# wordle_display.net
KiCad netlist of a schematic drawn in EAGLE
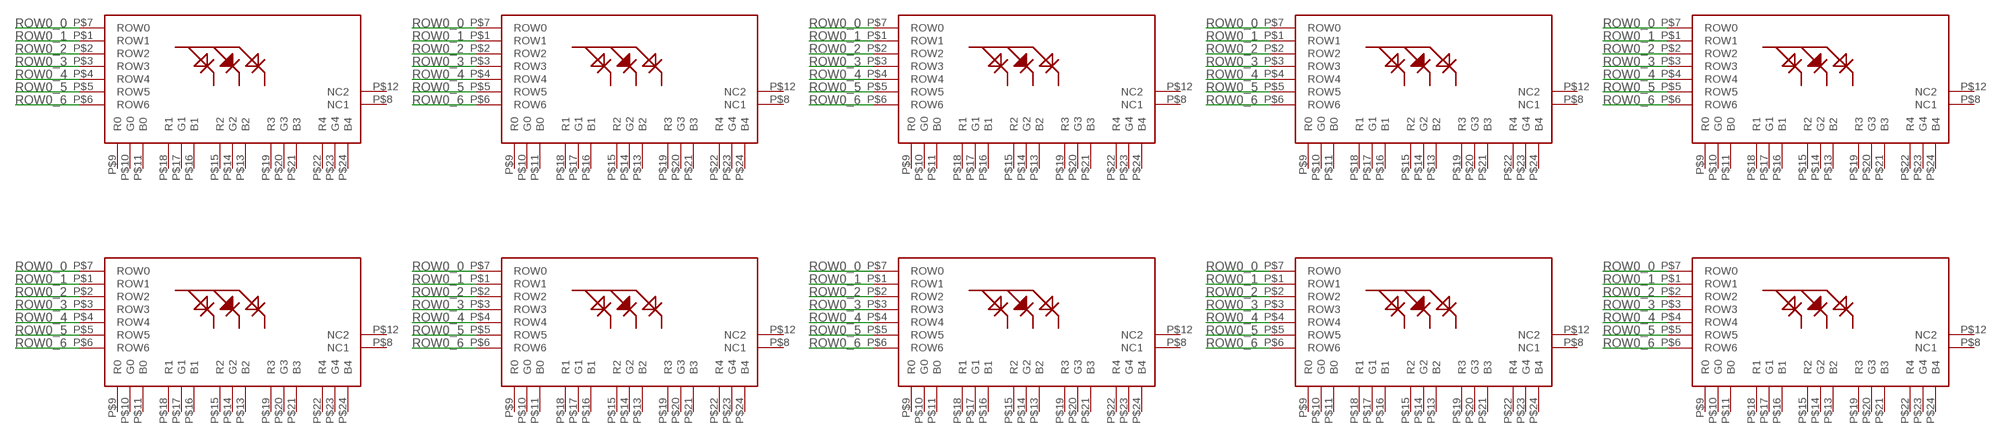
[diagram p0: schematic, sheet 1]

(export (version "E")
  (design (tool "Eeschema 10.0.6"))
  (components
    (comp (ref "U$1")
      (value "AE-UDOTMATRIX5X7-RGB")
      (footprint "eagle-import:AE-UDOTMATRIX5X7-RGB")
      (libsource (lib "eagle-import") (part "AE-UDOTMATRIX5X7-RGB"))
    )
    (comp (ref "U$2")
      (value "AE-UDOTMATRIX5X7-RGB")
      (footprint "eagle-import:AE-UDOTMATRIX5X7-RGB")
      (libsource (lib "eagle-import") (part "AE-UDOTMATRIX5X7-RGB"))
    )
    (comp (ref "U$3")
      (value "AE-UDOTMATRIX5X7-RGB")
      (footprint "eagle-import:AE-UDOTMATRIX5X7-RGB")
      (libsource (lib "eagle-import") (part "AE-UDOTMATRIX5X7-RGB"))
    )
    (comp (ref "U$4")
      (value "AE-UDOTMATRIX5X7-RGB")
      (footprint "eagle-import:AE-UDOTMATRIX5X7-RGB")
      (libsource (lib "eagle-import") (part "AE-UDOTMATRIX5X7-RGB"))
    )
    (comp (ref "U$5")
      (value "AE-UDOTMATRIX5X7-RGB")
      (footprint "eagle-import:AE-UDOTMATRIX5X7-RGB")
      (libsource (lib "eagle-import") (part "AE-UDOTMATRIX5X7-RGB"))
    )
    (comp (ref "U$6")
      (value "AE-UDOTMATRIX5X7-RGB")
      (footprint "eagle-import:AE-UDOTMATRIX5X7-RGB")
      (libsource (lib "eagle-import") (part "AE-UDOTMATRIX5X7-RGB"))
    )
    (comp (ref "U$7")
      (value "AE-UDOTMATRIX5X7-RGB")
      (footprint "eagle-import:AE-UDOTMATRIX5X7-RGB")
      (libsource (lib "eagle-import") (part "AE-UDOTMATRIX5X7-RGB"))
    )
    (comp (ref "U$8")
      (value "AE-UDOTMATRIX5X7-RGB")
      (footprint "eagle-import:AE-UDOTMATRIX5X7-RGB")
      (libsource (lib "eagle-import") (part "AE-UDOTMATRIX5X7-RGB"))
    )
    (comp (ref "U$9")
      (value "AE-UDOTMATRIX5X7-RGB")
      (footprint "eagle-import:AE-UDOTMATRIX5X7-RGB")
      (libsource (lib "eagle-import") (part "AE-UDOTMATRIX5X7-RGB"))
    )
    (comp (ref "U$10")
      (value "AE-UDOTMATRIX5X7-RGB")
      (footprint "eagle-import:AE-UDOTMATRIX5X7-RGB")
      (libsource (lib "eagle-import") (part "AE-UDOTMATRIX5X7-RGB"))
    )
  )
  (nets
    (net (code "1") (name "/ROW0_0") (class "Default")
      (node (ref "U$1") (pin "P$7") (pinfunction "ROW0_P$7") (pintype "bidirectional"))
      (node (ref "U$10") (pin "P$7") (pinfunction "ROW0_P$7") (pintype "bidirectional"))
      (node (ref "U$2") (pin "P$7") (pinfunction "ROW0_P$7") (pintype "bidirectional"))
      (node (ref "U$3") (pin "P$7") (pinfunction "ROW0_P$7") (pintype "bidirectional"))
      (node (ref "U$4") (pin "P$7") (pinfunction "ROW0_P$7") (pintype "bidirectional"))
      (node (ref "U$5") (pin "P$7") (pinfunction "ROW0_P$7") (pintype "bidirectional"))
      (node (ref "U$6") (pin "P$7") (pinfunction "ROW0_P$7") (pintype "bidirectional"))
      (node (ref "U$7") (pin "P$7") (pinfunction "ROW0_P$7") (pintype "bidirectional"))
      (node (ref "U$8") (pin "P$7") (pinfunction "ROW0_P$7") (pintype "bidirectional"))
      (node (ref "U$9") (pin "P$7") (pinfunction "ROW0_P$7") (pintype "bidirectional"))
    )
    (net (code "2") (name "/ROW0_1") (class "Default")
      (node (ref "U$1") (pin "P$1") (pinfunction "ROW1_P$1") (pintype "bidirectional"))
      (node (ref "U$10") (pin "P$1") (pinfunction "ROW1_P$1") (pintype "bidirectional"))
      (node (ref "U$2") (pin "P$1") (pinfunction "ROW1_P$1") (pintype "bidirectional"))
      (node (ref "U$3") (pin "P$1") (pinfunction "ROW1_P$1") (pintype "bidirectional"))
      (node (ref "U$4") (pin "P$1") (pinfunction "ROW1_P$1") (pintype "bidirectional"))
      (node (ref "U$5") (pin "P$1") (pinfunction "ROW1_P$1") (pintype "bidirectional"))
      (node (ref "U$6") (pin "P$1") (pinfunction "ROW1_P$1") (pintype "bidirectional"))
      (node (ref "U$7") (pin "P$1") (pinfunction "ROW1_P$1") (pintype "bidirectional"))
      (node (ref "U$8") (pin "P$1") (pinfunction "ROW1_P$1") (pintype "bidirectional"))
      (node (ref "U$9") (pin "P$1") (pinfunction "ROW1_P$1") (pintype "bidirectional"))
    )
    (net (code "3") (name "/ROW0_2") (class "Default")
      (node (ref "U$1") (pin "P$2") (pinfunction "ROW2_P$2") (pintype "bidirectional"))
      (node (ref "U$10") (pin "P$2") (pinfunction "ROW2_P$2") (pintype "bidirectional"))
      (node (ref "U$2") (pin "P$2") (pinfunction "ROW2_P$2") (pintype "bidirectional"))
      (node (ref "U$3") (pin "P$2") (pinfunction "ROW2_P$2") (pintype "bidirectional"))
      (node (ref "U$4") (pin "P$2") (pinfunction "ROW2_P$2") (pintype "bidirectional"))
      (node (ref "U$5") (pin "P$2") (pinfunction "ROW2_P$2") (pintype "bidirectional"))
      (node (ref "U$6") (pin "P$2") (pinfunction "ROW2_P$2") (pintype "bidirectional"))
      (node (ref "U$7") (pin "P$2") (pinfunction "ROW2_P$2") (pintype "bidirectional"))
      (node (ref "U$8") (pin "P$2") (pinfunction "ROW2_P$2") (pintype "bidirectional"))
      (node (ref "U$9") (pin "P$2") (pinfunction "ROW2_P$2") (pintype "bidirectional"))
    )
    (net (code "4") (name "/ROW0_3") (class "Default")
      (node (ref "U$1") (pin "P$3") (pinfunction "ROW3_P$3") (pintype "bidirectional"))
      (node (ref "U$10") (pin "P$3") (pinfunction "ROW3_P$3") (pintype "bidirectional"))
      (node (ref "U$2") (pin "P$3") (pinfunction "ROW3_P$3") (pintype "bidirectional"))
      (node (ref "U$3") (pin "P$3") (pinfunction "ROW3_P$3") (pintype "bidirectional"))
      (node (ref "U$4") (pin "P$3") (pinfunction "ROW3_P$3") (pintype "bidirectional"))
      (node (ref "U$5") (pin "P$3") (pinfunction "ROW3_P$3") (pintype "bidirectional"))
      (node (ref "U$6") (pin "P$3") (pinfunction "ROW3_P$3") (pintype "bidirectional"))
      (node (ref "U$7") (pin "P$3") (pinfunction "ROW3_P$3") (pintype "bidirectional"))
      (node (ref "U$8") (pin "P$3") (pinfunction "ROW3_P$3") (pintype "bidirectional"))
      (node (ref "U$9") (pin "P$3") (pinfunction "ROW3_P$3") (pintype "bidirectional"))
    )
    (net (code "5") (name "/ROW0_4") (class "Default")
      (node (ref "U$1") (pin "P$4") (pinfunction "ROW4_P$4") (pintype "bidirectional"))
      (node (ref "U$10") (pin "P$4") (pinfunction "ROW4_P$4") (pintype "bidirectional"))
      (node (ref "U$2") (pin "P$4") (pinfunction "ROW4_P$4") (pintype "bidirectional"))
      (node (ref "U$3") (pin "P$4") (pinfunction "ROW4_P$4") (pintype "bidirectional"))
      (node (ref "U$4") (pin "P$4") (pinfunction "ROW4_P$4") (pintype "bidirectional"))
      (node (ref "U$5") (pin "P$4") (pinfunction "ROW4_P$4") (pintype "bidirectional"))
      (node (ref "U$6") (pin "P$4") (pinfunction "ROW4_P$4") (pintype "bidirectional"))
      (node (ref "U$7") (pin "P$4") (pinfunction "ROW4_P$4") (pintype "bidirectional"))
      (node (ref "U$8") (pin "P$4") (pinfunction "ROW4_P$4") (pintype "bidirectional"))
      (node (ref "U$9") (pin "P$4") (pinfunction "ROW4_P$4") (pintype "bidirectional"))
    )
    (net (code "6") (name "/ROW0_5") (class "Default")
      (node (ref "U$1") (pin "P$5") (pinfunction "ROW5_P$5") (pintype "bidirectional"))
      (node (ref "U$10") (pin "P$5") (pinfunction "ROW5_P$5") (pintype "bidirectional"))
      (node (ref "U$2") (pin "P$5") (pinfunction "ROW5_P$5") (pintype "bidirectional"))
      (node (ref "U$3") (pin "P$5") (pinfunction "ROW5_P$5") (pintype "bidirectional"))
      (node (ref "U$4") (pin "P$5") (pinfunction "ROW5_P$5") (pintype "bidirectional"))
      (node (ref "U$5") (pin "P$5") (pinfunction "ROW5_P$5") (pintype "bidirectional"))
      (node (ref "U$6") (pin "P$5") (pinfunction "ROW5_P$5") (pintype "bidirectional"))
      (node (ref "U$7") (pin "P$5") (pinfunction "ROW5_P$5") (pintype "bidirectional"))
      (node (ref "U$8") (pin "P$5") (pinfunction "ROW5_P$5") (pintype "bidirectional"))
      (node (ref "U$9") (pin "P$5") (pinfunction "ROW5_P$5") (pintype "bidirectional"))
    )
    (net (code "7") (name "/ROW0_6") (class "Default")
      (node (ref "U$1") (pin "P$6") (pinfunction "ROW6_P$6") (pintype "bidirectional"))
      (node (ref "U$10") (pin "P$6") (pinfunction "ROW6_P$6") (pintype "bidirectional"))
      (node (ref "U$2") (pin "P$6") (pinfunction "ROW6_P$6") (pintype "bidirectional"))
      (node (ref "U$3") (pin "P$6") (pinfunction "ROW6_P$6") (pintype "bidirectional"))
      (node (ref "U$4") (pin "P$6") (pinfunction "ROW6_P$6") (pintype "bidirectional"))
      (node (ref "U$5") (pin "P$6") (pinfunction "ROW6_P$6") (pintype "bidirectional"))
      (node (ref "U$6") (pin "P$6") (pinfunction "ROW6_P$6") (pintype "bidirectional"))
      (node (ref "U$7") (pin "P$6") (pinfunction "ROW6_P$6") (pintype "bidirectional"))
      (node (ref "U$8") (pin "P$6") (pinfunction "ROW6_P$6") (pintype "bidirectional"))
      (node (ref "U$9") (pin "P$6") (pinfunction "ROW6_P$6") (pintype "bidirectional"))
    )
    (net (code "8") (name "unconnected-(U$1-B0-PadP$11)") (class "Default")
      (node (ref "U$1") (pin "P$11") (pinfunction "B0_P$11") (pintype "bidirectional"))
    )
    (net (code "9") (name "unconnected-(U$1-B1-PadP$16)") (class "Default")
      (node (ref "U$1") (pin "P$16") (pinfunction "B1_P$16") (pintype "bidirectional"))
    )
    (net (code "10") (name "unconnected-(U$1-B2-PadP$13)") (class "Default")
      (node (ref "U$1") (pin "P$13") (pinfunction "B2_P$13") (pintype "bidirectional"))
    )
    (net (code "11") (name "unconnected-(U$1-B3-PadP$21)") (class "Default")
      (node (ref "U$1") (pin "P$21") (pinfunction "B3_P$21") (pintype "bidirectional"))
    )
    (net (code "12") (name "unconnected-(U$1-B4-PadP$24)") (class "Default")
      (node (ref "U$1") (pin "P$24") (pinfunction "B4_P$24") (pintype "bidirectional"))
    )
    (net (code "13") (name "unconnected-(U$1-G0-PadP$10)") (class "Default")
      (node (ref "U$1") (pin "P$10") (pinfunction "G0_P$10") (pintype "bidirectional"))
    )
    (net (code "14") (name "unconnected-(U$1-G1-PadP$17)") (class "Default")
      (node (ref "U$1") (pin "P$17") (pinfunction "G1_P$17") (pintype "bidirectional"))
    )
    (net (code "15") (name "unconnected-(U$1-G2-PadP$14)") (class "Default")
      (node (ref "U$1") (pin "P$14") (pinfunction "G2_P$14") (pintype "bidirectional"))
    )
    (net (code "16") (name "unconnected-(U$1-G3-PadP$20)") (class "Default")
      (node (ref "U$1") (pin "P$20") (pinfunction "G3_P$20") (pintype "bidirectional"))
    )
    (net (code "17") (name "unconnected-(U$1-G4-PadP$23)") (class "Default")
      (node (ref "U$1") (pin "P$23") (pinfunction "G4_P$23") (pintype "bidirectional"))
    )
    (net (code "18") (name "unconnected-(U$1-NC1-PadP$8)") (class "Default")
      (node (ref "U$1") (pin "P$8") (pinfunction "NC1_P$8") (pintype "no_connect"))
    )
    (net (code "19") (name "unconnected-(U$1-NC2-PadP$12)") (class "Default")
      (node (ref "U$1") (pin "P$12") (pinfunction "NC2_P$12") (pintype "no_connect"))
    )
    (net (code "20") (name "unconnected-(U$1-R0-PadP$9)") (class "Default")
      (node (ref "U$1") (pin "P$9") (pinfunction "R0_P$9") (pintype "bidirectional"))
    )
    (net (code "21") (name "unconnected-(U$1-R1-PadP$18)") (class "Default")
      (node (ref "U$1") (pin "P$18") (pinfunction "R1_P$18") (pintype "bidirectional"))
    )
    (net (code "22") (name "unconnected-(U$1-R2-PadP$15)") (class "Default")
      (node (ref "U$1") (pin "P$15") (pinfunction "R2_P$15") (pintype "bidirectional"))
    )
    (net (code "23") (name "unconnected-(U$1-R3-PadP$19)") (class "Default")
      (node (ref "U$1") (pin "P$19") (pinfunction "R3_P$19") (pintype "bidirectional"))
    )
    (net (code "24") (name "unconnected-(U$1-R4-PadP$22)") (class "Default")
      (node (ref "U$1") (pin "P$22") (pinfunction "R4_P$22") (pintype "bidirectional"))
    )
    (net (code "25") (name "unconnected-(U$2-B0-PadP$11)") (class "Default")
      (node (ref "U$2") (pin "P$11") (pinfunction "B0_P$11") (pintype "bidirectional"))
    )
    (net (code "26") (name "unconnected-(U$2-B1-PadP$16)") (class "Default")
      (node (ref "U$2") (pin "P$16") (pinfunction "B1_P$16") (pintype "bidirectional"))
    )
    (net (code "27") (name "unconnected-(U$2-B2-PadP$13)") (class "Default")
      (node (ref "U$2") (pin "P$13") (pinfunction "B2_P$13") (pintype "bidirectional"))
    )
    (net (code "28") (name "unconnected-(U$2-B3-PadP$21)") (class "Default")
      (node (ref "U$2") (pin "P$21") (pinfunction "B3_P$21") (pintype "bidirectional"))
    )
    (net (code "29") (name "unconnected-(U$2-B4-PadP$24)") (class "Default")
      (node (ref "U$2") (pin "P$24") (pinfunction "B4_P$24") (pintype "bidirectional"))
    )
    (net (code "30") (name "unconnected-(U$2-G0-PadP$10)") (class "Default")
      (node (ref "U$2") (pin "P$10") (pinfunction "G0_P$10") (pintype "bidirectional"))
    )
    (net (code "31") (name "unconnected-(U$2-G1-PadP$17)") (class "Default")
      (node (ref "U$2") (pin "P$17") (pinfunction "G1_P$17") (pintype "bidirectional"))
    )
    (net (code "32") (name "unconnected-(U$2-G2-PadP$14)") (class "Default")
      (node (ref "U$2") (pin "P$14") (pinfunction "G2_P$14") (pintype "bidirectional"))
    )
    (net (code "33") (name "unconnected-(U$2-G3-PadP$20)") (class "Default")
      (node (ref "U$2") (pin "P$20") (pinfunction "G3_P$20") (pintype "bidirectional"))
    )
    (net (code "34") (name "unconnected-(U$2-G4-PadP$23)") (class "Default")
      (node (ref "U$2") (pin "P$23") (pinfunction "G4_P$23") (pintype "bidirectional"))
    )
    (net (code "35") (name "unconnected-(U$2-NC1-PadP$8)") (class "Default")
      (node (ref "U$2") (pin "P$8") (pinfunction "NC1_P$8") (pintype "no_connect"))
    )
    (net (code "36") (name "unconnected-(U$2-NC2-PadP$12)") (class "Default")
      (node (ref "U$2") (pin "P$12") (pinfunction "NC2_P$12") (pintype "no_connect"))
    )
    (net (code "37") (name "unconnected-(U$2-R0-PadP$9)") (class "Default")
      (node (ref "U$2") (pin "P$9") (pinfunction "R0_P$9") (pintype "bidirectional"))
    )
    (net (code "38") (name "unconnected-(U$2-R1-PadP$18)") (class "Default")
      (node (ref "U$2") (pin "P$18") (pinfunction "R1_P$18") (pintype "bidirectional"))
    )
    (net (code "39") (name "unconnected-(U$2-R2-PadP$15)") (class "Default")
      (node (ref "U$2") (pin "P$15") (pinfunction "R2_P$15") (pintype "bidirectional"))
    )
    (net (code "40") (name "unconnected-(U$2-R3-PadP$19)") (class "Default")
      (node (ref "U$2") (pin "P$19") (pinfunction "R3_P$19") (pintype "bidirectional"))
    )
    (net (code "41") (name "unconnected-(U$2-R4-PadP$22)") (class "Default")
      (node (ref "U$2") (pin "P$22") (pinfunction "R4_P$22") (pintype "bidirectional"))
    )
    (net (code "42") (name "unconnected-(U$3-B0-PadP$11)") (class "Default")
      (node (ref "U$3") (pin "P$11") (pinfunction "B0_P$11") (pintype "bidirectional"))
    )
    (net (code "43") (name "unconnected-(U$3-B1-PadP$16)") (class "Default")
      (node (ref "U$3") (pin "P$16") (pinfunction "B1_P$16") (pintype "bidirectional"))
    )
    (net (code "44") (name "unconnected-(U$3-B2-PadP$13)") (class "Default")
      (node (ref "U$3") (pin "P$13") (pinfunction "B2_P$13") (pintype "bidirectional"))
    )
    (net (code "45") (name "unconnected-(U$3-B3-PadP$21)") (class "Default")
      (node (ref "U$3") (pin "P$21") (pinfunction "B3_P$21") (pintype "bidirectional"))
    )
    (net (code "46") (name "unconnected-(U$3-B4-PadP$24)") (class "Default")
      (node (ref "U$3") (pin "P$24") (pinfunction "B4_P$24") (pintype "bidirectional"))
    )
    (net (code "47") (name "unconnected-(U$3-G0-PadP$10)") (class "Default")
      (node (ref "U$3") (pin "P$10") (pinfunction "G0_P$10") (pintype "bidirectional"))
    )
    (net (code "48") (name "unconnected-(U$3-G1-PadP$17)") (class "Default")
      (node (ref "U$3") (pin "P$17") (pinfunction "G1_P$17") (pintype "bidirectional"))
    )
    (net (code "49") (name "unconnected-(U$3-G2-PadP$14)") (class "Default")
      (node (ref "U$3") (pin "P$14") (pinfunction "G2_P$14") (pintype "bidirectional"))
    )
    (net (code "50") (name "unconnected-(U$3-G3-PadP$20)") (class "Default")
      (node (ref "U$3") (pin "P$20") (pinfunction "G3_P$20") (pintype "bidirectional"))
    )
    (net (code "51") (name "unconnected-(U$3-G4-PadP$23)") (class "Default")
      (node (ref "U$3") (pin "P$23") (pinfunction "G4_P$23") (pintype "bidirectional"))
    )
    (net (code "52") (name "unconnected-(U$3-NC1-PadP$8)") (class "Default")
      (node (ref "U$3") (pin "P$8") (pinfunction "NC1_P$8") (pintype "no_connect"))
    )
    (net (code "53") (name "unconnected-(U$3-NC2-PadP$12)") (class "Default")
      (node (ref "U$3") (pin "P$12") (pinfunction "NC2_P$12") (pintype "no_connect"))
    )
    (net (code "54") (name "unconnected-(U$3-R0-PadP$9)") (class "Default")
      (node (ref "U$3") (pin "P$9") (pinfunction "R0_P$9") (pintype "bidirectional"))
    )
    (net (code "55") (name "unconnected-(U$3-R1-PadP$18)") (class "Default")
      (node (ref "U$3") (pin "P$18") (pinfunction "R1_P$18") (pintype "bidirectional"))
    )
    (net (code "56") (name "unconnected-(U$3-R2-PadP$15)") (class "Default")
      (node (ref "U$3") (pin "P$15") (pinfunction "R2_P$15") (pintype "bidirectional"))
    )
    (net (code "57") (name "unconnected-(U$3-R3-PadP$19)") (class "Default")
      (node (ref "U$3") (pin "P$19") (pinfunction "R3_P$19") (pintype "bidirectional"))
    )
    (net (code "58") (name "unconnected-(U$3-R4-PadP$22)") (class "Default")
      (node (ref "U$3") (pin "P$22") (pinfunction "R4_P$22") (pintype "bidirectional"))
    )
    (net (code "59") (name "unconnected-(U$4-B0-PadP$11)") (class "Default")
      (node (ref "U$4") (pin "P$11") (pinfunction "B0_P$11") (pintype "bidirectional"))
    )
    (net (code "60") (name "unconnected-(U$4-B1-PadP$16)") (class "Default")
      (node (ref "U$4") (pin "P$16") (pinfunction "B1_P$16") (pintype "bidirectional"))
    )
    (net (code "61") (name "unconnected-(U$4-B2-PadP$13)") (class "Default")
      (node (ref "U$4") (pin "P$13") (pinfunction "B2_P$13") (pintype "bidirectional"))
    )
    (net (code "62") (name "unconnected-(U$4-B3-PadP$21)") (class "Default")
      (node (ref "U$4") (pin "P$21") (pinfunction "B3_P$21") (pintype "bidirectional"))
    )
    (net (code "63") (name "unconnected-(U$4-B4-PadP$24)") (class "Default")
      (node (ref "U$4") (pin "P$24") (pinfunction "B4_P$24") (pintype "bidirectional"))
    )
    (net (code "64") (name "unconnected-(U$4-G0-PadP$10)") (class "Default")
      (node (ref "U$4") (pin "P$10") (pinfunction "G0_P$10") (pintype "bidirectional"))
    )
    (net (code "65") (name "unconnected-(U$4-G1-PadP$17)") (class "Default")
      (node (ref "U$4") (pin "P$17") (pinfunction "G1_P$17") (pintype "bidirectional"))
    )
    (net (code "66") (name "unconnected-(U$4-G2-PadP$14)") (class "Default")
      (node (ref "U$4") (pin "P$14") (pinfunction "G2_P$14") (pintype "bidirectional"))
    )
    (net (code "67") (name "unconnected-(U$4-G3-PadP$20)") (class "Default")
      (node (ref "U$4") (pin "P$20") (pinfunction "G3_P$20") (pintype "bidirectional"))
    )
    (net (code "68") (name "unconnected-(U$4-G4-PadP$23)") (class "Default")
      (node (ref "U$4") (pin "P$23") (pinfunction "G4_P$23") (pintype "bidirectional"))
    )
    (net (code "69") (name "unconnected-(U$4-NC1-PadP$8)") (class "Default")
      (node (ref "U$4") (pin "P$8") (pinfunction "NC1_P$8") (pintype "no_connect"))
    )
    (net (code "70") (name "unconnected-(U$4-NC2-PadP$12)") (class "Default")
      (node (ref "U$4") (pin "P$12") (pinfunction "NC2_P$12") (pintype "no_connect"))
    )
    (net (code "71") (name "unconnected-(U$4-R0-PadP$9)") (class "Default")
      (node (ref "U$4") (pin "P$9") (pinfunction "R0_P$9") (pintype "bidirectional"))
    )
    (net (code "72") (name "unconnected-(U$4-R1-PadP$18)") (class "Default")
      (node (ref "U$4") (pin "P$18") (pinfunction "R1_P$18") (pintype "bidirectional"))
    )
    (net (code "73") (name "unconnected-(U$4-R2-PadP$15)") (class "Default")
      (node (ref "U$4") (pin "P$15") (pinfunction "R2_P$15") (pintype "bidirectional"))
    )
    (net (code "74") (name "unconnected-(U$4-R3-PadP$19)") (class "Default")
      (node (ref "U$4") (pin "P$19") (pinfunction "R3_P$19") (pintype "bidirectional"))
    )
    (net (code "75") (name "unconnected-(U$4-R4-PadP$22)") (class "Default")
      (node (ref "U$4") (pin "P$22") (pinfunction "R4_P$22") (pintype "bidirectional"))
    )
    (net (code "76") (name "unconnected-(U$5-B0-PadP$11)") (class "Default")
      (node (ref "U$5") (pin "P$11") (pinfunction "B0_P$11") (pintype "bidirectional"))
    )
    (net (code "77") (name "unconnected-(U$5-B1-PadP$16)") (class "Default")
      (node (ref "U$5") (pin "P$16") (pinfunction "B1_P$16") (pintype "bidirectional"))
    )
    (net (code "78") (name "unconnected-(U$5-B2-PadP$13)") (class "Default")
      (node (ref "U$5") (pin "P$13") (pinfunction "B2_P$13") (pintype "bidirectional"))
    )
    (net (code "79") (name "unconnected-(U$5-B3-PadP$21)") (class "Default")
      (node (ref "U$5") (pin "P$21") (pinfunction "B3_P$21") (pintype "bidirectional"))
    )
    (net (code "80") (name "unconnected-(U$5-B4-PadP$24)") (class "Default")
      (node (ref "U$5") (pin "P$24") (pinfunction "B4_P$24") (pintype "bidirectional"))
    )
    (net (code "81") (name "unconnected-(U$5-G0-PadP$10)") (class "Default")
      (node (ref "U$5") (pin "P$10") (pinfunction "G0_P$10") (pintype "bidirectional"))
    )
    (net (code "82") (name "unconnected-(U$5-G1-PadP$17)") (class "Default")
      (node (ref "U$5") (pin "P$17") (pinfunction "G1_P$17") (pintype "bidirectional"))
    )
    (net (code "83") (name "unconnected-(U$5-G2-PadP$14)") (class "Default")
      (node (ref "U$5") (pin "P$14") (pinfunction "G2_P$14") (pintype "bidirectional"))
    )
    (net (code "84") (name "unconnected-(U$5-G3-PadP$20)") (class "Default")
      (node (ref "U$5") (pin "P$20") (pinfunction "G3_P$20") (pintype "bidirectional"))
    )
    (net (code "85") (name "unconnected-(U$5-G4-PadP$23)") (class "Default")
      (node (ref "U$5") (pin "P$23") (pinfunction "G4_P$23") (pintype "bidirectional"))
    )
    (net (code "86") (name "unconnected-(U$5-NC1-PadP$8)") (class "Default")
      (node (ref "U$5") (pin "P$8") (pinfunction "NC1_P$8") (pintype "no_connect"))
    )
    (net (code "87") (name "unconnected-(U$5-NC2-PadP$12)") (class "Default")
      (node (ref "U$5") (pin "P$12") (pinfunction "NC2_P$12") (pintype "no_connect"))
    )
    (net (code "88") (name "unconnected-(U$5-R0-PadP$9)") (class "Default")
      (node (ref "U$5") (pin "P$9") (pinfunction "R0_P$9") (pintype "bidirectional"))
    )
    (net (code "89") (name "unconnected-(U$5-R1-PadP$18)") (class "Default")
      (node (ref "U$5") (pin "P$18") (pinfunction "R1_P$18") (pintype "bidirectional"))
    )
    (net (code "90") (name "unconnected-(U$5-R2-PadP$15)") (class "Default")
      (node (ref "U$5") (pin "P$15") (pinfunction "R2_P$15") (pintype "bidirectional"))
    )
    (net (code "91") (name "unconnected-(U$5-R3-PadP$19)") (class "Default")
      (node (ref "U$5") (pin "P$19") (pinfunction "R3_P$19") (pintype "bidirectional"))
    )
    (net (code "92") (name "unconnected-(U$5-R4-PadP$22)") (class "Default")
      (node (ref "U$5") (pin "P$22") (pinfunction "R4_P$22") (pintype "bidirectional"))
    )
    (net (code "93") (name "unconnected-(U$6-B0-PadP$11)") (class "Default")
      (node (ref "U$6") (pin "P$11") (pinfunction "B0_P$11") (pintype "bidirectional"))
    )
    (net (code "94") (name "unconnected-(U$6-B1-PadP$16)") (class "Default")
      (node (ref "U$6") (pin "P$16") (pinfunction "B1_P$16") (pintype "bidirectional"))
    )
    (net (code "95") (name "unconnected-(U$6-B2-PadP$13)") (class "Default")
      (node (ref "U$6") (pin "P$13") (pinfunction "B2_P$13") (pintype "bidirectional"))
    )
    (net (code "96") (name "unconnected-(U$6-B3-PadP$21)") (class "Default")
      (node (ref "U$6") (pin "P$21") (pinfunction "B3_P$21") (pintype "bidirectional"))
    )
    (net (code "97") (name "unconnected-(U$6-B4-PadP$24)") (class "Default")
      (node (ref "U$6") (pin "P$24") (pinfunction "B4_P$24") (pintype "bidirectional"))
    )
    (net (code "98") (name "unconnected-(U$6-G0-PadP$10)") (class "Default")
      (node (ref "U$6") (pin "P$10") (pinfunction "G0_P$10") (pintype "bidirectional"))
    )
    (net (code "99") (name "unconnected-(U$6-G1-PadP$17)") (class "Default")
      (node (ref "U$6") (pin "P$17") (pinfunction "G1_P$17") (pintype "bidirectional"))
    )
    (net (code "100") (name "unconnected-(U$6-G2-PadP$14)") (class "Default")
      (node (ref "U$6") (pin "P$14") (pinfunction "G2_P$14") (pintype "bidirectional"))
    )
    (net (code "101") (name "unconnected-(U$6-G3-PadP$20)") (class "Default")
      (node (ref "U$6") (pin "P$20") (pinfunction "G3_P$20") (pintype "bidirectional"))
    )
    (net (code "102") (name "unconnected-(U$6-G4-PadP$23)") (class "Default")
      (node (ref "U$6") (pin "P$23") (pinfunction "G4_P$23") (pintype "bidirectional"))
    )
    (net (code "103") (name "unconnected-(U$6-NC1-PadP$8)") (class "Default")
      (node (ref "U$6") (pin "P$8") (pinfunction "NC1_P$8") (pintype "no_connect"))
    )
    (net (code "104") (name "unconnected-(U$6-NC2-PadP$12)") (class "Default")
      (node (ref "U$6") (pin "P$12") (pinfunction "NC2_P$12") (pintype "no_connect"))
    )
    (net (code "105") (name "unconnected-(U$6-R0-PadP$9)") (class "Default")
      (node (ref "U$6") (pin "P$9") (pinfunction "R0_P$9") (pintype "bidirectional"))
    )
    (net (code "106") (name "unconnected-(U$6-R1-PadP$18)") (class "Default")
      (node (ref "U$6") (pin "P$18") (pinfunction "R1_P$18") (pintype "bidirectional"))
    )
    (net (code "107") (name "unconnected-(U$6-R2-PadP$15)") (class "Default")
      (node (ref "U$6") (pin "P$15") (pinfunction "R2_P$15") (pintype "bidirectional"))
    )
    (net (code "108") (name "unconnected-(U$6-R3-PadP$19)") (class "Default")
      (node (ref "U$6") (pin "P$19") (pinfunction "R3_P$19") (pintype "bidirectional"))
    )
    (net (code "109") (name "unconnected-(U$6-R4-PadP$22)") (class "Default")
      (node (ref "U$6") (pin "P$22") (pinfunction "R4_P$22") (pintype "bidirectional"))
    )
    (net (code "110") (name "unconnected-(U$7-B0-PadP$11)") (class "Default")
      (node (ref "U$7") (pin "P$11") (pinfunction "B0_P$11") (pintype "bidirectional"))
    )
    (net (code "111") (name "unconnected-(U$7-B1-PadP$16)") (class "Default")
      (node (ref "U$7") (pin "P$16") (pinfunction "B1_P$16") (pintype "bidirectional"))
    )
    (net (code "112") (name "unconnected-(U$7-B2-PadP$13)") (class "Default")
      (node (ref "U$7") (pin "P$13") (pinfunction "B2_P$13") (pintype "bidirectional"))
    )
    (net (code "113") (name "unconnected-(U$7-B3-PadP$21)") (class "Default")
      (node (ref "U$7") (pin "P$21") (pinfunction "B3_P$21") (pintype "bidirectional"))
    )
    (net (code "114") (name "unconnected-(U$7-B4-PadP$24)") (class "Default")
      (node (ref "U$7") (pin "P$24") (pinfunction "B4_P$24") (pintype "bidirectional"))
    )
    (net (code "115") (name "unconnected-(U$7-G0-PadP$10)") (class "Default")
      (node (ref "U$7") (pin "P$10") (pinfunction "G0_P$10") (pintype "bidirectional"))
    )
    (net (code "116") (name "unconnected-(U$7-G1-PadP$17)") (class "Default")
      (node (ref "U$7") (pin "P$17") (pinfunction "G1_P$17") (pintype "bidirectional"))
    )
    (net (code "117") (name "unconnected-(U$7-G2-PadP$14)") (class "Default")
      (node (ref "U$7") (pin "P$14") (pinfunction "G2_P$14") (pintype "bidirectional"))
    )
    (net (code "118") (name "unconnected-(U$7-G3-PadP$20)") (class "Default")
      (node (ref "U$7") (pin "P$20") (pinfunction "G3_P$20") (pintype "bidirectional"))
    )
    (net (code "119") (name "unconnected-(U$7-G4-PadP$23)") (class "Default")
      (node (ref "U$7") (pin "P$23") (pinfunction "G4_P$23") (pintype "bidirectional"))
    )
    (net (code "120") (name "unconnected-(U$7-NC1-PadP$8)") (class "Default")
      (node (ref "U$7") (pin "P$8") (pinfunction "NC1_P$8") (pintype "no_connect"))
    )
    (net (code "121") (name "unconnected-(U$7-NC2-PadP$12)") (class "Default")
      (node (ref "U$7") (pin "P$12") (pinfunction "NC2_P$12") (pintype "no_connect"))
    )
    (net (code "122") (name "unconnected-(U$7-R0-PadP$9)") (class "Default")
      (node (ref "U$7") (pin "P$9") (pinfunction "R0_P$9") (pintype "bidirectional"))
    )
    (net (code "123") (name "unconnected-(U$7-R1-PadP$18)") (class "Default")
      (node (ref "U$7") (pin "P$18") (pinfunction "R1_P$18") (pintype "bidirectional"))
    )
    (net (code "124") (name "unconnected-(U$7-R2-PadP$15)") (class "Default")
      (node (ref "U$7") (pin "P$15") (pinfunction "R2_P$15") (pintype "bidirectional"))
    )
    (net (code "125") (name "unconnected-(U$7-R3-PadP$19)") (class "Default")
      (node (ref "U$7") (pin "P$19") (pinfunction "R3_P$19") (pintype "bidirectional"))
    )
    (net (code "126") (name "unconnected-(U$7-R4-PadP$22)") (class "Default")
      (node (ref "U$7") (pin "P$22") (pinfunction "R4_P$22") (pintype "bidirectional"))
    )
    (net (code "127") (name "unconnected-(U$8-B0-PadP$11)") (class "Default")
      (node (ref "U$8") (pin "P$11") (pinfunction "B0_P$11") (pintype "bidirectional"))
    )
    (net (code "128") (name "unconnected-(U$8-B1-PadP$16)") (class "Default")
      (node (ref "U$8") (pin "P$16") (pinfunction "B1_P$16") (pintype "bidirectional"))
    )
    (net (code "129") (name "unconnected-(U$8-B2-PadP$13)") (class "Default")
      (node (ref "U$8") (pin "P$13") (pinfunction "B2_P$13") (pintype "bidirectional"))
    )
    (net (code "130") (name "unconnected-(U$8-B3-PadP$21)") (class "Default")
      (node (ref "U$8") (pin "P$21") (pinfunction "B3_P$21") (pintype "bidirectional"))
    )
    (net (code "131") (name "unconnected-(U$8-B4-PadP$24)") (class "Default")
      (node (ref "U$8") (pin "P$24") (pinfunction "B4_P$24") (pintype "bidirectional"))
    )
    (net (code "132") (name "unconnected-(U$8-G0-PadP$10)") (class "Default")
      (node (ref "U$8") (pin "P$10") (pinfunction "G0_P$10") (pintype "bidirectional"))
    )
    (net (code "133") (name "unconnected-(U$8-G1-PadP$17)") (class "Default")
      (node (ref "U$8") (pin "P$17") (pinfunction "G1_P$17") (pintype "bidirectional"))
    )
    (net (code "134") (name "unconnected-(U$8-G2-PadP$14)") (class "Default")
      (node (ref "U$8") (pin "P$14") (pinfunction "G2_P$14") (pintype "bidirectional"))
    )
    (net (code "135") (name "unconnected-(U$8-G3-PadP$20)") (class "Default")
      (node (ref "U$8") (pin "P$20") (pinfunction "G3_P$20") (pintype "bidirectional"))
    )
    (net (code "136") (name "unconnected-(U$8-G4-PadP$23)") (class "Default")
      (node (ref "U$8") (pin "P$23") (pinfunction "G4_P$23") (pintype "bidirectional"))
    )
    (net (code "137") (name "unconnected-(U$8-NC1-PadP$8)") (class "Default")
      (node (ref "U$8") (pin "P$8") (pinfunction "NC1_P$8") (pintype "no_connect"))
    )
    (net (code "138") (name "unconnected-(U$8-NC2-PadP$12)") (class "Default")
      (node (ref "U$8") (pin "P$12") (pinfunction "NC2_P$12") (pintype "no_connect"))
    )
    (net (code "139") (name "unconnected-(U$8-R0-PadP$9)") (class "Default")
      (node (ref "U$8") (pin "P$9") (pinfunction "R0_P$9") (pintype "bidirectional"))
    )
    (net (code "140") (name "unconnected-(U$8-R1-PadP$18)") (class "Default")
      (node (ref "U$8") (pin "P$18") (pinfunction "R1_P$18") (pintype "bidirectional"))
    )
    (net (code "141") (name "unconnected-(U$8-R2-PadP$15)") (class "Default")
      (node (ref "U$8") (pin "P$15") (pinfunction "R2_P$15") (pintype "bidirectional"))
    )
    (net (code "142") (name "unconnected-(U$8-R3-PadP$19)") (class "Default")
      (node (ref "U$8") (pin "P$19") (pinfunction "R3_P$19") (pintype "bidirectional"))
    )
    (net (code "143") (name "unconnected-(U$8-R4-PadP$22)") (class "Default")
      (node (ref "U$8") (pin "P$22") (pinfunction "R4_P$22") (pintype "bidirectional"))
    )
    (net (code "144") (name "unconnected-(U$9-B0-PadP$11)") (class "Default")
      (node (ref "U$9") (pin "P$11") (pinfunction "B0_P$11") (pintype "bidirectional"))
    )
    (net (code "145") (name "unconnected-(U$9-B1-PadP$16)") (class "Default")
      (node (ref "U$9") (pin "P$16") (pinfunction "B1_P$16") (pintype "bidirectional"))
    )
    (net (code "146") (name "unconnected-(U$9-B2-PadP$13)") (class "Default")
      (node (ref "U$9") (pin "P$13") (pinfunction "B2_P$13") (pintype "bidirectional"))
    )
    (net (code "147") (name "unconnected-(U$9-B3-PadP$21)") (class "Default")
      (node (ref "U$9") (pin "P$21") (pinfunction "B3_P$21") (pintype "bidirectional"))
    )
    (net (code "148") (name "unconnected-(U$9-B4-PadP$24)") (class "Default")
      (node (ref "U$9") (pin "P$24") (pinfunction "B4_P$24") (pintype "bidirectional"))
    )
    (net (code "149") (name "unconnected-(U$9-G0-PadP$10)") (class "Default")
      (node (ref "U$9") (pin "P$10") (pinfunction "G0_P$10") (pintype "bidirectional"))
    )
    (net (code "150") (name "unconnected-(U$9-G1-PadP$17)") (class "Default")
      (node (ref "U$9") (pin "P$17") (pinfunction "G1_P$17") (pintype "bidirectional"))
    )
    (net (code "151") (name "unconnected-(U$9-G2-PadP$14)") (class "Default")
      (node (ref "U$9") (pin "P$14") (pinfunction "G2_P$14") (pintype "bidirectional"))
    )
    (net (code "152") (name "unconnected-(U$9-G3-PadP$20)") (class "Default")
      (node (ref "U$9") (pin "P$20") (pinfunction "G3_P$20") (pintype "bidirectional"))
    )
    (net (code "153") (name "unconnected-(U$9-G4-PadP$23)") (class "Default")
      (node (ref "U$9") (pin "P$23") (pinfunction "G4_P$23") (pintype "bidirectional"))
    )
    (net (code "154") (name "unconnected-(U$9-NC1-PadP$8)") (class "Default")
      (node (ref "U$9") (pin "P$8") (pinfunction "NC1_P$8") (pintype "no_connect"))
    )
    (net (code "155") (name "unconnected-(U$9-NC2-PadP$12)") (class "Default")
      (node (ref "U$9") (pin "P$12") (pinfunction "NC2_P$12") (pintype "no_connect"))
    )
    (net (code "156") (name "unconnected-(U$9-R0-PadP$9)") (class "Default")
      (node (ref "U$9") (pin "P$9") (pinfunction "R0_P$9") (pintype "bidirectional"))
    )
    (net (code "157") (name "unconnected-(U$9-R1-PadP$18)") (class "Default")
      (node (ref "U$9") (pin "P$18") (pinfunction "R1_P$18") (pintype "bidirectional"))
    )
    (net (code "158") (name "unconnected-(U$9-R2-PadP$15)") (class "Default")
      (node (ref "U$9") (pin "P$15") (pinfunction "R2_P$15") (pintype "bidirectional"))
    )
    (net (code "159") (name "unconnected-(U$9-R3-PadP$19)") (class "Default")
      (node (ref "U$9") (pin "P$19") (pinfunction "R3_P$19") (pintype "bidirectional"))
    )
    (net (code "160") (name "unconnected-(U$9-R4-PadP$22)") (class "Default")
      (node (ref "U$9") (pin "P$22") (pinfunction "R4_P$22") (pintype "bidirectional"))
    )
    (net (code "161") (name "unconnected-(U$10-B0-PadP$11)") (class "Default")
      (node (ref "U$10") (pin "P$11") (pinfunction "B0_P$11") (pintype "bidirectional"))
    )
    (net (code "162") (name "unconnected-(U$10-B1-PadP$16)") (class "Default")
      (node (ref "U$10") (pin "P$16") (pinfunction "B1_P$16") (pintype "bidirectional"))
    )
    (net (code "163") (name "unconnected-(U$10-B2-PadP$13)") (class "Default")
      (node (ref "U$10") (pin "P$13") (pinfunction "B2_P$13") (pintype "bidirectional"))
    )
    (net (code "164") (name "unconnected-(U$10-B3-PadP$21)") (class "Default")
      (node (ref "U$10") (pin "P$21") (pinfunction "B3_P$21") (pintype "bidirectional"))
    )
    (net (code "165") (name "unconnected-(U$10-B4-PadP$24)") (class "Default")
      (node (ref "U$10") (pin "P$24") (pinfunction "B4_P$24") (pintype "bidirectional"))
    )
    (net (code "166") (name "unconnected-(U$10-G0-PadP$10)") (class "Default")
      (node (ref "U$10") (pin "P$10") (pinfunction "G0_P$10") (pintype "bidirectional"))
    )
    (net (code "167") (name "unconnected-(U$10-G1-PadP$17)") (class "Default")
      (node (ref "U$10") (pin "P$17") (pinfunction "G1_P$17") (pintype "bidirectional"))
    )
    (net (code "168") (name "unconnected-(U$10-G2-PadP$14)") (class "Default")
      (node (ref "U$10") (pin "P$14") (pinfunction "G2_P$14") (pintype "bidirectional"))
    )
    (net (code "169") (name "unconnected-(U$10-G3-PadP$20)") (class "Default")
      (node (ref "U$10") (pin "P$20") (pinfunction "G3_P$20") (pintype "bidirectional"))
    )
    (net (code "170") (name "unconnected-(U$10-G4-PadP$23)") (class "Default")
      (node (ref "U$10") (pin "P$23") (pinfunction "G4_P$23") (pintype "bidirectional"))
    )
    (net (code "171") (name "unconnected-(U$10-NC1-PadP$8)") (class "Default")
      (node (ref "U$10") (pin "P$8") (pinfunction "NC1_P$8") (pintype "no_connect"))
    )
    (net (code "172") (name "unconnected-(U$10-NC2-PadP$12)") (class "Default")
      (node (ref "U$10") (pin "P$12") (pinfunction "NC2_P$12") (pintype "no_connect"))
    )
    (net (code "173") (name "unconnected-(U$10-R0-PadP$9)") (class "Default")
      (node (ref "U$10") (pin "P$9") (pinfunction "R0_P$9") (pintype "bidirectional"))
    )
    (net (code "174") (name "unconnected-(U$10-R1-PadP$18)") (class "Default")
      (node (ref "U$10") (pin "P$18") (pinfunction "R1_P$18") (pintype "bidirectional"))
    )
    (net (code "175") (name "unconnected-(U$10-R2-PadP$15)") (class "Default")
      (node (ref "U$10") (pin "P$15") (pinfunction "R2_P$15") (pintype "bidirectional"))
    )
    (net (code "176") (name "unconnected-(U$10-R3-PadP$19)") (class "Default")
      (node (ref "U$10") (pin "P$19") (pinfunction "R3_P$19") (pintype "bidirectional"))
    )
    (net (code "177") (name "unconnected-(U$10-R4-PadP$22)") (class "Default")
      (node (ref "U$10") (pin "P$22") (pinfunction "R4_P$22") (pintype "bidirectional"))
    )
  )
)
